# ddpd.net
KiCad netlist of a schematic drawn in EAGLE
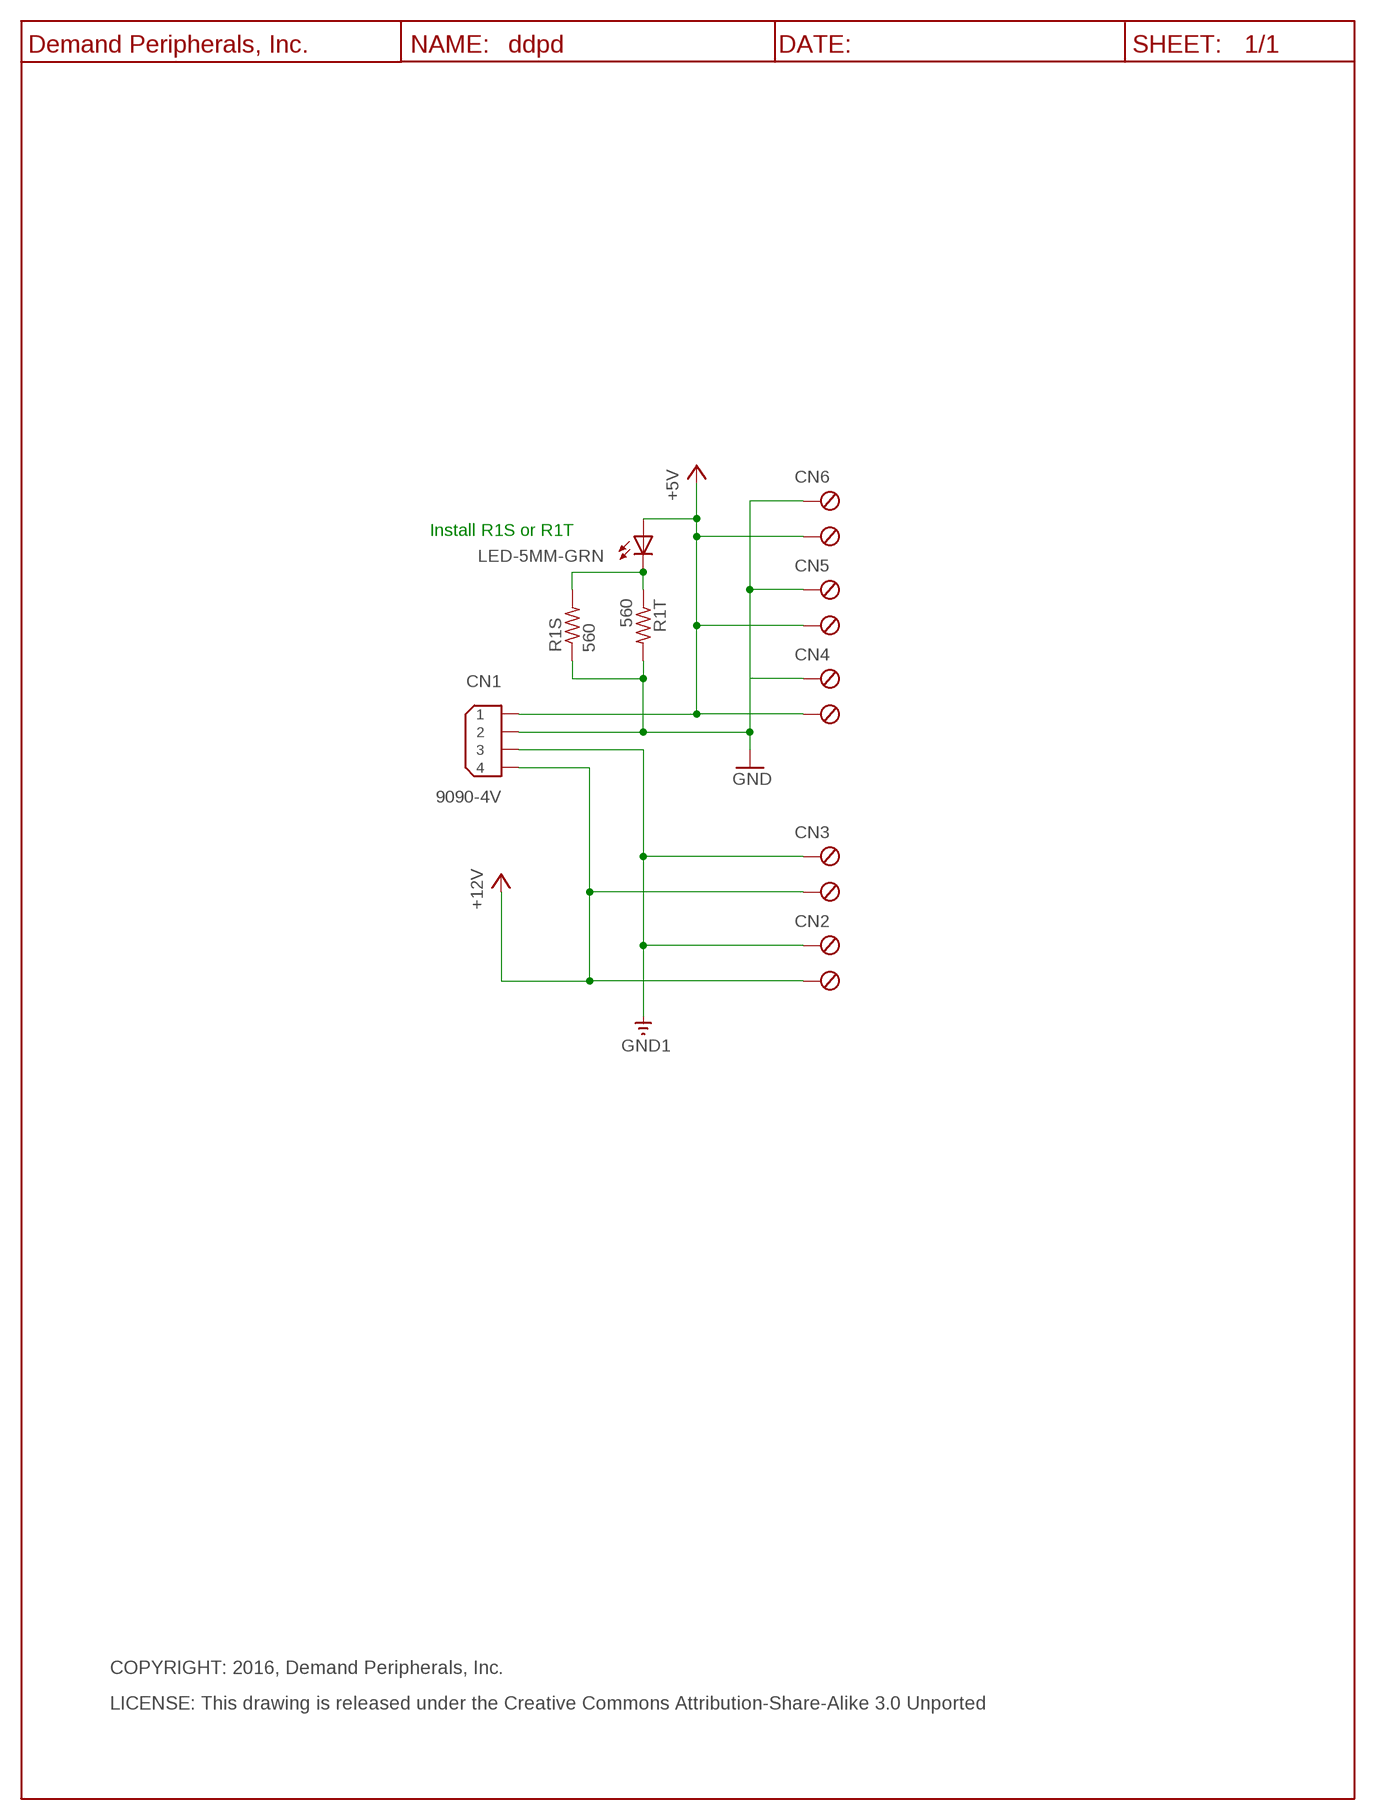
[diagram p0: schematic, sheet 1]

(export (version "E")
  (design (tool "Eeschema 10.0.6"))
  (components
    (comp (ref "+5V")
      (value "LED-5MM-GRN")
      (footprint "eagle-import:LED5MM")
      (libsource (lib "eagle-import") (part "LED-5MM-GRN"))
    )
    (comp (ref "CN1")
      (value "9090-4V")
      (footprint "eagle-import:9090-4R")
      (libsource (lib "eagle-import") (part "9090-4R"))
    )
    (comp (ref "CN2")
      (value "TBLK-5.08-X2")
      (footprint "eagle-import:TBLK-5.08-X2")
      (libsource (lib "eagle-import") (part "TBLK-5.08-X2"))
    )
    (comp (ref "CN3")
      (value "TBLK-5.08-X2")
      (footprint "eagle-import:TBLK-5.08-X2")
      (libsource (lib "eagle-import") (part "TBLK-5.08-X2"))
    )
    (comp (ref "CN4")
      (value "TBLK-5.08-X2")
      (footprint "eagle-import:TBLK-5.08-X2")
      (libsource (lib "eagle-import") (part "TBLK-5.08-X2"))
    )
    (comp (ref "CN5")
      (value "TBLK-5.08-X2")
      (footprint "eagle-import:TBLK-5.08-X2")
      (libsource (lib "eagle-import") (part "TBLK-5.08-X2"))
    )
    (comp (ref "CN6")
      (value "TBLK-5.08-X2")
      (footprint "eagle-import:TBLK-5.08-X2")
      (libsource (lib "eagle-import") (part "TBLK-5.08-X2"))
    )
    (comp (ref "R1S")
      (value "560")
      (footprint "eagle-import:R0603")
      (libsource (lib "eagle-import") (part "R560_R0603"))
    )
    (comp (ref "R1T")
      (value "560")
      (footprint "eagle-import:R4TENTHS")
      (libsource (lib "eagle-import") (part "R560_"))
    )
    (comp (ref "U$4")
      (value "DP_FRAME_P")
      (footprint "eagle-import:LETTER_P")
      (libsource (lib "eagle-import") (part "DP_FRAME_P"))
    )
  )
  (nets
    (net (code "1") (name "+5V") (class "Default")
      (node (ref "+5V") (pin "A") (pinfunction "A_A") (pintype "passive"))
      (node (ref "CN1") (pin "1") (pinfunction "1_1") (pintype "passive"))
      (node (ref "CN4") (pin "2") (pinfunction "KL1_2") (pintype "passive"))
      (node (ref "CN5") (pin "2") (pinfunction "KL1_2") (pintype "passive"))
      (node (ref "CN6") (pin "2") (pinfunction "KL1_2") (pintype "passive"))
    )
    (net (code "2") (name "+12V") (class "Default")
      (node (ref "CN1") (pin "4") (pinfunction "4_4") (pintype "passive"))
      (node (ref "CN2") (pin "2") (pinfunction "KL1_2") (pintype "passive"))
      (node (ref "CN3") (pin "2") (pinfunction "KL1_2") (pintype "passive"))
    )
    (net (code "3") (name "GND") (class "Default")
      (node (ref "CN1") (pin "2") (pinfunction "2_2") (pintype "passive"))
      (node (ref "CN4") (pin "1") (pinfunction "KL_1") (pintype "passive"))
      (node (ref "CN5") (pin "1") (pinfunction "KL_1") (pintype "passive"))
      (node (ref "CN6") (pin "1") (pinfunction "KL_1") (pintype "passive"))
      (node (ref "R1S") (pin "1") (pinfunction "1_1") (pintype "passive"))
      (node (ref "R1T") (pin "2") (pinfunction "2_2") (pintype "passive"))
    )
    (net (code "4") (name "GND1") (class "Default")
      (node (ref "CN1") (pin "3") (pinfunction "3_3") (pintype "passive"))
      (node (ref "CN2") (pin "1") (pinfunction "KL_1") (pintype "passive"))
      (node (ref "CN3") (pin "1") (pinfunction "KL_1") (pintype "passive"))
    )
    (net (code "5") (name "Net-(+5V-PadC)") (class "Default")
      (node (ref "+5V") (pin "C") (pinfunction "C_C") (pintype "passive"))
      (node (ref "R1S") (pin "2") (pinfunction "2_2") (pintype "passive"))
      (node (ref "R1T") (pin "1") (pinfunction "1_1") (pintype "passive"))
    )
  )
)
